# 2x6x1_27mm-pogo-adapter-mk-1_0_1.net
KiCad netlist of a schematic drawn in EAGLE
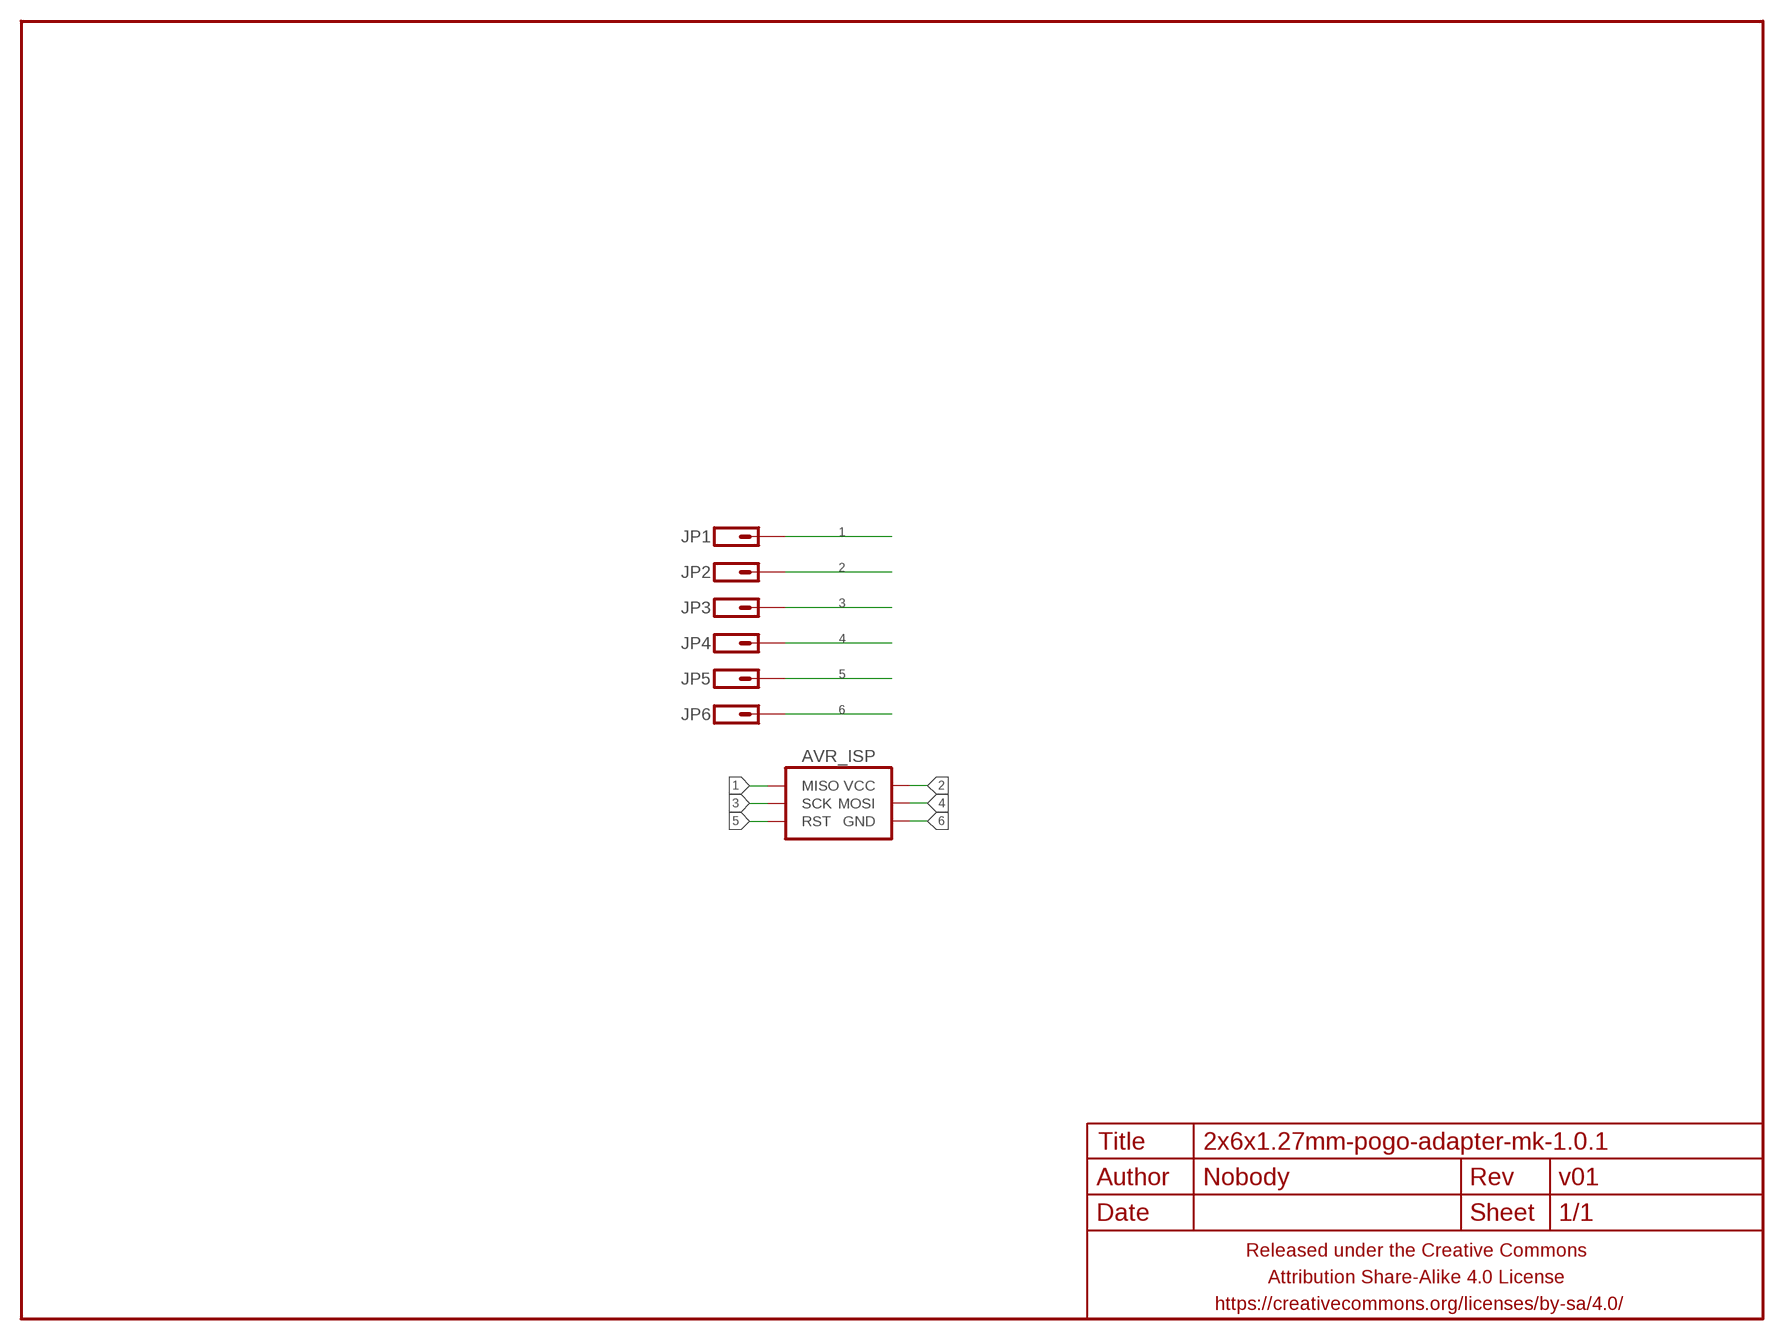
[diagram p0: schematic, sheet 1]

(export (version "E")
  (design (tool "Eeschema 10.0.6"))
  (components
    (comp (ref "AVR_ISP")
      (value "AVR_SPI_PRG_62X3_SMD")
      (footprint "eagle-import:2X3_SMD")
      (libsource (lib "eagle-import") (part "AVR_SPI_PRG_62X3_SMD"))
    )
    (comp (ref "FRAME1")
      (value "FRAME-LETTERNO_PACKAGE")
      (footprint "eagle-import:DUMMY")
      (fields (field (name "DESIGNER") "Nobody") (field (name "VERSION") "v01"))
      (libsource (lib "eagle-import") (part "FRAME-LETTERNO_PACKAGE"))
    )
    (comp (ref "JP1")
      (value "M01PTH-0.7MM-CIR-NS")
      (footprint "eagle-import:1X01-0.7MM-CIR-NS")
      (libsource (lib "eagle-import") (part "M01PTH-0.7MM-CIR-NS"))
    )
    (comp (ref "JP2")
      (value "M01PTH-0.65MM-NS")
      (footprint "eagle-import:1X01_635MM")
      (libsource (lib "eagle-import") (part "M01PTH-0.65MM-NS"))
    )
    (comp (ref "JP3")
      (value "M01PTH-0.65MM-NS")
      (footprint "eagle-import:1X01_635MM")
      (libsource (lib "eagle-import") (part "M01PTH-0.65MM-NS"))
    )
    (comp (ref "JP4")
      (value "M01PTH-0.65MM-NS")
      (footprint "eagle-import:1X01_635MM")
      (libsource (lib "eagle-import") (part "M01PTH-0.65MM-NS"))
    )
    (comp (ref "JP5")
      (value "M01PTH-0.65MM-NS")
      (footprint "eagle-import:1X01_635MM")
      (libsource (lib "eagle-import") (part "M01PTH-0.65MM-NS"))
    )
    (comp (ref "JP6")
      (value "M01PTH-0.65MM-NS")
      (footprint "eagle-import:1X01_635MM")
      (libsource (lib "eagle-import") (part "M01PTH-0.65MM-NS"))
    )
  )
  (nets
    (net (code "1") (name "1") (class "Default")
      (node (ref "AVR_ISP") (pin "1") (pinfunction "MISO_1") (pintype "passive"))
      (node (ref "JP1") (pin "P$1") (pinfunction "1_P$1") (pintype "passive"))
    )
    (net (code "2") (name "2") (class "Default")
      (node (ref "AVR_ISP") (pin "2") (pinfunction "VCC_2") (pintype "passive"))
      (node (ref "JP2") (pin "P$1") (pinfunction "1_P$1") (pintype "passive"))
    )
    (net (code "3") (name "3") (class "Default")
      (node (ref "AVR_ISP") (pin "3") (pinfunction "SCK_3") (pintype "passive"))
      (node (ref "JP3") (pin "P$1") (pinfunction "1_P$1") (pintype "passive"))
    )
    (net (code "4") (name "4") (class "Default")
      (node (ref "AVR_ISP") (pin "4") (pinfunction "MOSI_4") (pintype "passive"))
      (node (ref "JP4") (pin "P$1") (pinfunction "1_P$1") (pintype "passive"))
    )
    (net (code "5") (name "5") (class "Default")
      (node (ref "AVR_ISP") (pin "5") (pinfunction "RST_5") (pintype "passive"))
      (node (ref "JP5") (pin "P$1") (pinfunction "1_P$1") (pintype "passive"))
    )
    (net (code "6") (name "6") (class "Default")
      (node (ref "AVR_ISP") (pin "6") (pinfunction "GND_6") (pintype "passive"))
      (node (ref "JP6") (pin "P$1") (pinfunction "1_P$1") (pintype "passive"))
    )
  )
)
